# connector.net
KiCad netlist of a schematic drawn in Altium Designer
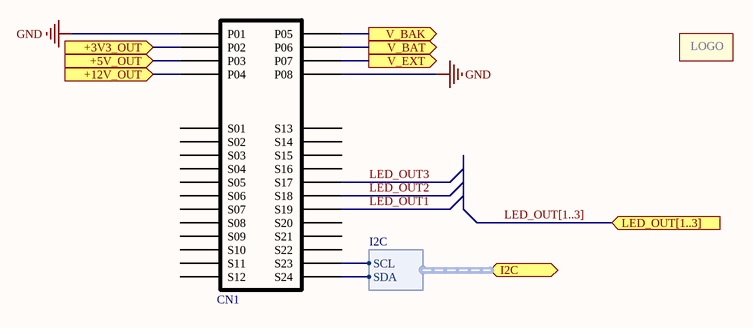
[diagram p0: connector.SchDoc]

(export (version "E")
  (design (tool "Eeschema 10.0.6"))
  (components
    (comp (ref "CN1")
      (value "4-24-4-Connector")
      (footprint "ET60T-04-24-04-L-RT1-gp")
      (description "Samtec Connector")
      (libsource (lib "bitbots") (part "ET60T-04-24-04-L-RT1-GP"))
    )
    (comp (ref "Logo1")
      (value "Hamburg Bit-Bots Logo")
      (footprint "Logo")
      (libsource (lib "bitbots") (part "Logo"))
    )
  )
  (nets
    (net (code "2") (name "/+3V3_OUT") (class "Default")
      (node (ref "CN1") (pin "P02") (pinfunction "P02_P02") (pintype "passive"))
    )
    (net (code "3") (name "/+5V_OUT") (class "Default")
      (node (ref "CN1") (pin "P03") (pinfunction "P03_P03") (pintype "passive"))
    )
    (net (code "4") (name "/+12V_OUT") (class "Default")
      (node (ref "CN1") (pin "P04") (pinfunction "P04_P04") (pintype "passive"))
    )
    (net (code "5") (name "/LED_OUT1") (class "Default")
      (node (ref "CN1") (pin "S19") (pinfunction "S19_S19") (pintype "passive"))
    )
    (net (code "6") (name "/LED_OUT2") (class "Default")
      (node (ref "CN1") (pin "S18") (pinfunction "S18_S18") (pintype "passive"))
    )
    (net (code "7") (name "/LED_OUT3") (class "Default")
      (node (ref "CN1") (pin "S17") (pinfunction "S17_S17") (pintype "passive"))
    )
    (net (code "9") (name "/SCL") (class "Default")
      (node (ref "CN1") (pin "S23") (pinfunction "S23_S23") (pintype "passive"))
    )
    (net (code "10") (name "/SDA") (class "Default")
      (node (ref "CN1") (pin "S24") (pinfunction "S24_S24") (pintype "passive"))
    )
    (net (code "11") (name "/V_BAK") (class "Default")
      (node (ref "CN1") (pin "P05") (pinfunction "P05_P05") (pintype "passive"))
    )
    (net (code "12") (name "/V_BAT") (class "Default")
      (node (ref "CN1") (pin "P06") (pinfunction "P06_P06") (pintype "passive"))
    )
    (net (code "13") (name "/V_EXT") (class "Default")
      (node (ref "CN1") (pin "P07") (pinfunction "P07_P07") (pintype "passive"))
    )
    (net (code "15") (name "GND") (class "Default")
      (node (ref "CN1") (pin "P01") (pinfunction "P01_P01") (pintype "passive"))
      (node (ref "CN1") (pin "P08") (pinfunction "P08_P08") (pintype "passive"))
    )
    (net (code "16") (name "unconnected-(CN1-PadS01)") (class "Default")
      (node (ref "CN1") (pin "S01") (pinfunction "S01_S01") (pintype "passive"))
    )
    (net (code "17") (name "unconnected-(CN1-PadS02)") (class "Default")
      (node (ref "CN1") (pin "S02") (pinfunction "S02_S02") (pintype "passive"))
    )
    (net (code "18") (name "unconnected-(CN1-PadS03)") (class "Default")
      (node (ref "CN1") (pin "S03") (pinfunction "S03_S03") (pintype "passive"))
    )
    (net (code "19") (name "unconnected-(CN1-PadS04)") (class "Default")
      (node (ref "CN1") (pin "S04") (pinfunction "S04_S04") (pintype "passive"))
    )
    (net (code "20") (name "unconnected-(CN1-PadS05)") (class "Default")
      (node (ref "CN1") (pin "S05") (pinfunction "S05_S05") (pintype "passive"))
    )
    (net (code "21") (name "unconnected-(CN1-PadS06)") (class "Default")
      (node (ref "CN1") (pin "S06") (pinfunction "S06_S06") (pintype "passive"))
    )
    (net (code "22") (name "unconnected-(CN1-PadS07)") (class "Default")
      (node (ref "CN1") (pin "S07") (pinfunction "S07_S07") (pintype "passive"))
    )
    (net (code "23") (name "unconnected-(CN1-PadS08)") (class "Default")
      (node (ref "CN1") (pin "S08") (pinfunction "S08_S08") (pintype "passive"))
    )
    (net (code "24") (name "unconnected-(CN1-PadS09)") (class "Default")
      (node (ref "CN1") (pin "S09") (pinfunction "S09_S09") (pintype "passive"))
    )
    (net (code "25") (name "unconnected-(CN1-PadS10)") (class "Default")
      (node (ref "CN1") (pin "S10") (pinfunction "S10_S10") (pintype "passive"))
    )
    (net (code "26") (name "unconnected-(CN1-PadS11)") (class "Default")
      (node (ref "CN1") (pin "S11") (pinfunction "S11_S11") (pintype "passive"))
    )
    (net (code "27") (name "unconnected-(CN1-PadS12)") (class "Default")
      (node (ref "CN1") (pin "S12") (pinfunction "S12_S12") (pintype "passive"))
    )
    (net (code "28") (name "unconnected-(CN1-PadS13)") (class "Default")
      (node (ref "CN1") (pin "S13") (pinfunction "S13_S13") (pintype "passive"))
    )
    (net (code "29") (name "unconnected-(CN1-PadS14)") (class "Default")
      (node (ref "CN1") (pin "S14") (pinfunction "S14_S14") (pintype "passive"))
    )
    (net (code "30") (name "unconnected-(CN1-PadS15)") (class "Default")
      (node (ref "CN1") (pin "S15") (pinfunction "S15_S15") (pintype "passive"))
    )
    (net (code "31") (name "unconnected-(CN1-PadS16)") (class "Default")
      (node (ref "CN1") (pin "S16") (pinfunction "S16_S16") (pintype "passive"))
    )
    (net (code "32") (name "unconnected-(CN1-PadS20)") (class "Default")
      (node (ref "CN1") (pin "S20") (pinfunction "S20_S20") (pintype "passive"))
    )
    (net (code "33") (name "unconnected-(CN1-PadS21)") (class "Default")
      (node (ref "CN1") (pin "S21") (pinfunction "S21_S21") (pintype "passive"))
    )
    (net (code "34") (name "unconnected-(CN1-PadS22)") (class "Default")
      (node (ref "CN1") (pin "S22") (pinfunction "S22_S22") (pintype "passive"))
    )
  )
)
